# Resistor_ladder.net
KiCad netlist of a schematic drawn in EAGLE
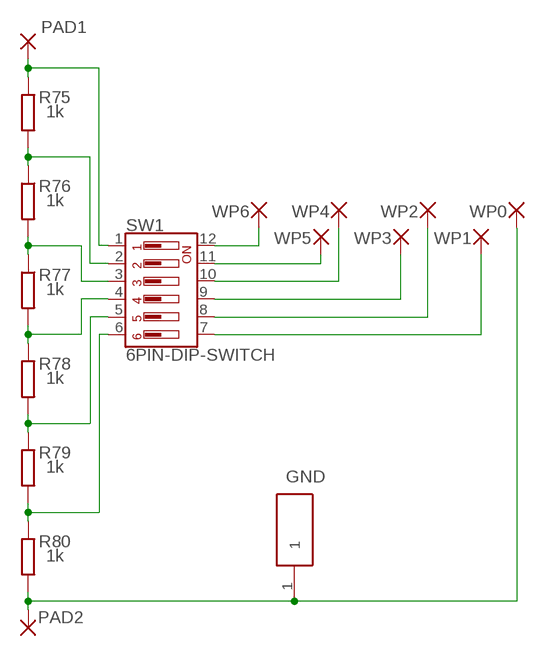
[diagram p0: schematic, sheet 1]

(export (version "E")
  (design (tool "Eeschema 10.0.6"))
  (components
    (comp (ref "GND")
      (value "5000")
      (footprint "eagle-import:5000")
      (libsource (lib "eagle-import") (part "5000"))
    )
    (comp (ref "PAD1")
      (value "SMD_PAD")
      (footprint "eagle-import:SMD_PAD")
      (libsource (lib "eagle-import") (part "SMD_PAD"))
    )
    (comp (ref "PAD2")
      (value "SMD_PAD")
      (footprint "eagle-import:SMD_PAD")
      (libsource (lib "eagle-import") (part "SMD_PAD"))
    )
    (comp (ref "R75")
      (value "1k")
      (footprint "eagle-import:R0603")
      (libsource (lib "eagle-import") (part "R-EU0603"))
    )
    (comp (ref "R76")
      (value "1k")
      (footprint "eagle-import:R0603")
      (libsource (lib "eagle-import") (part "R-EU0603"))
    )
    (comp (ref "R77")
      (value "1k")
      (footprint "eagle-import:R0603")
      (libsource (lib "eagle-import") (part "R-EU0603"))
    )
    (comp (ref "R78")
      (value "1k")
      (footprint "eagle-import:R0603")
      (libsource (lib "eagle-import") (part "R-EU0603"))
    )
    (comp (ref "R79")
      (value "1k")
      (footprint "eagle-import:R0603")
      (libsource (lib "eagle-import") (part "R-EU0603"))
    )
    (comp (ref "R80")
      (value "1k")
      (footprint "eagle-import:R0603")
      (libsource (lib "eagle-import") (part "R-EU0603"))
    )
    (comp (ref "SW1")
      (value "6PIN-DIP-SWITCH")
      (footprint "eagle-import:DIPSWITCH-06")
      (libsource (lib "eagle-import") (part "6PIN-DIP-SWITCH"))
    )
    (comp (ref "WP0")
      (value "2,54/1,1")
      (footprint "eagle-import:2,54_1,1")
      (libsource (lib "eagle-import") (part "2,54/1,1"))
    )
    (comp (ref "WP1")
      (value "2,54/1,1")
      (footprint "eagle-import:2,54_1,1")
      (libsource (lib "eagle-import") (part "2,54/1,1"))
    )
    (comp (ref "WP2")
      (value "2,54/1,1")
      (footprint "eagle-import:2,54_1,1")
      (libsource (lib "eagle-import") (part "2,54/1,1"))
    )
    (comp (ref "WP3")
      (value "2,54/1,1")
      (footprint "eagle-import:2,54_1,1")
      (libsource (lib "eagle-import") (part "2,54/1,1"))
    )
    (comp (ref "WP4")
      (value "2,54/1,1")
      (footprint "eagle-import:2,54_1,1")
      (libsource (lib "eagle-import") (part "2,54/1,1"))
    )
    (comp (ref "WP5")
      (value "2,54/1,1")
      (footprint "eagle-import:2,54_1,1")
      (libsource (lib "eagle-import") (part "2,54/1,1"))
    )
    (comp (ref "WP6")
      (value "2,54/1,1")
      (footprint "eagle-import:2,54_1,1")
      (libsource (lib "eagle-import") (part "2,54/1,1"))
    )
  )
  (nets
    (net (code "1") (name "Net-(PAD1-P)") (class "Default")
      (node (ref "PAD1") (pin "1") (pinfunction "P_1") (pintype "passive"))
      (node (ref "R75") (pin "1") (pinfunction "1_1") (pintype "passive"))
      (node (ref "SW1") (pin "1") (pinfunction "1_1") (pintype "bidirectional"))
    )
    (net (code "2") (name "Net-(PAD2-P)") (class "Default")
      (node (ref "GND") (pin "1") (pinfunction "1_1") (pintype "bidirectional"))
      (node (ref "PAD2") (pin "1") (pinfunction "P_1") (pintype "passive"))
      (node (ref "R80") (pin "2") (pinfunction "2_2") (pintype "passive"))
      (node (ref "WP0") (pin "1") (pinfunction "P_1") (pintype "passive"))
    )
    (net (code "3") (name "Net-(R75-Pad2)") (class "Default")
      (node (ref "R75") (pin "2") (pinfunction "2_2") (pintype "passive"))
      (node (ref "R76") (pin "1") (pinfunction "1_1") (pintype "passive"))
      (node (ref "SW1") (pin "2") (pinfunction "2_2") (pintype "bidirectional"))
    )
    (net (code "4") (name "Net-(R76-Pad2)") (class "Default")
      (node (ref "R76") (pin "2") (pinfunction "2_2") (pintype "passive"))
      (node (ref "R77") (pin "1") (pinfunction "1_1") (pintype "passive"))
      (node (ref "SW1") (pin "3") (pinfunction "3_3") (pintype "bidirectional"))
    )
    (net (code "5") (name "Net-(R77-Pad2)") (class "Default")
      (node (ref "R77") (pin "2") (pinfunction "2_2") (pintype "passive"))
      (node (ref "R78") (pin "1") (pinfunction "1_1") (pintype "passive"))
      (node (ref "SW1") (pin "4") (pinfunction "4_4") (pintype "bidirectional"))
    )
    (net (code "6") (name "Net-(R78-Pad2)") (class "Default")
      (node (ref "R78") (pin "2") (pinfunction "2_2") (pintype "passive"))
      (node (ref "R79") (pin "1") (pinfunction "1_1") (pintype "passive"))
      (node (ref "SW1") (pin "5") (pinfunction "5_5") (pintype "bidirectional"))
    )
    (net (code "7") (name "Net-(R79-Pad2)") (class "Default")
      (node (ref "R79") (pin "2") (pinfunction "2_2") (pintype "passive"))
      (node (ref "R80") (pin "1") (pinfunction "1_1") (pintype "passive"))
      (node (ref "SW1") (pin "6") (pinfunction "6_6") (pintype "bidirectional"))
    )
    (net (code "8") (name "Net-(WP1-P)") (class "Default")
      (node (ref "SW1") (pin "7") (pinfunction "7_7") (pintype "bidirectional"))
      (node (ref "WP1") (pin "1") (pinfunction "P_1") (pintype "passive"))
    )
    (net (code "9") (name "Net-(WP2-P)") (class "Default")
      (node (ref "SW1") (pin "8") (pinfunction "8_8") (pintype "bidirectional"))
      (node (ref "WP2") (pin "1") (pinfunction "P_1") (pintype "passive"))
    )
    (net (code "10") (name "Net-(WP3-P)") (class "Default")
      (node (ref "SW1") (pin "9") (pinfunction "9_9") (pintype "bidirectional"))
      (node (ref "WP3") (pin "1") (pinfunction "P_1") (pintype "passive"))
    )
    (net (code "11") (name "Net-(WP4-P)") (class "Default")
      (node (ref "SW1") (pin "10") (pinfunction "10_10") (pintype "bidirectional"))
      (node (ref "WP4") (pin "1") (pinfunction "P_1") (pintype "passive"))
    )
    (net (code "12") (name "Net-(WP5-P)") (class "Default")
      (node (ref "SW1") (pin "11") (pinfunction "11_11") (pintype "bidirectional"))
      (node (ref "WP5") (pin "1") (pinfunction "P_1") (pintype "passive"))
    )
    (net (code "13") (name "Net-(WP6-P)") (class "Default")
      (node (ref "SW1") (pin "12") (pinfunction "12_12") (pintype "bidirectional"))
      (node (ref "WP6") (pin "1") (pinfunction "P_1") (pintype "passive"))
    )
  )
)
